# XStick__XS1-L4.net
KiCad netlist of a schematic drawn in EAGLE
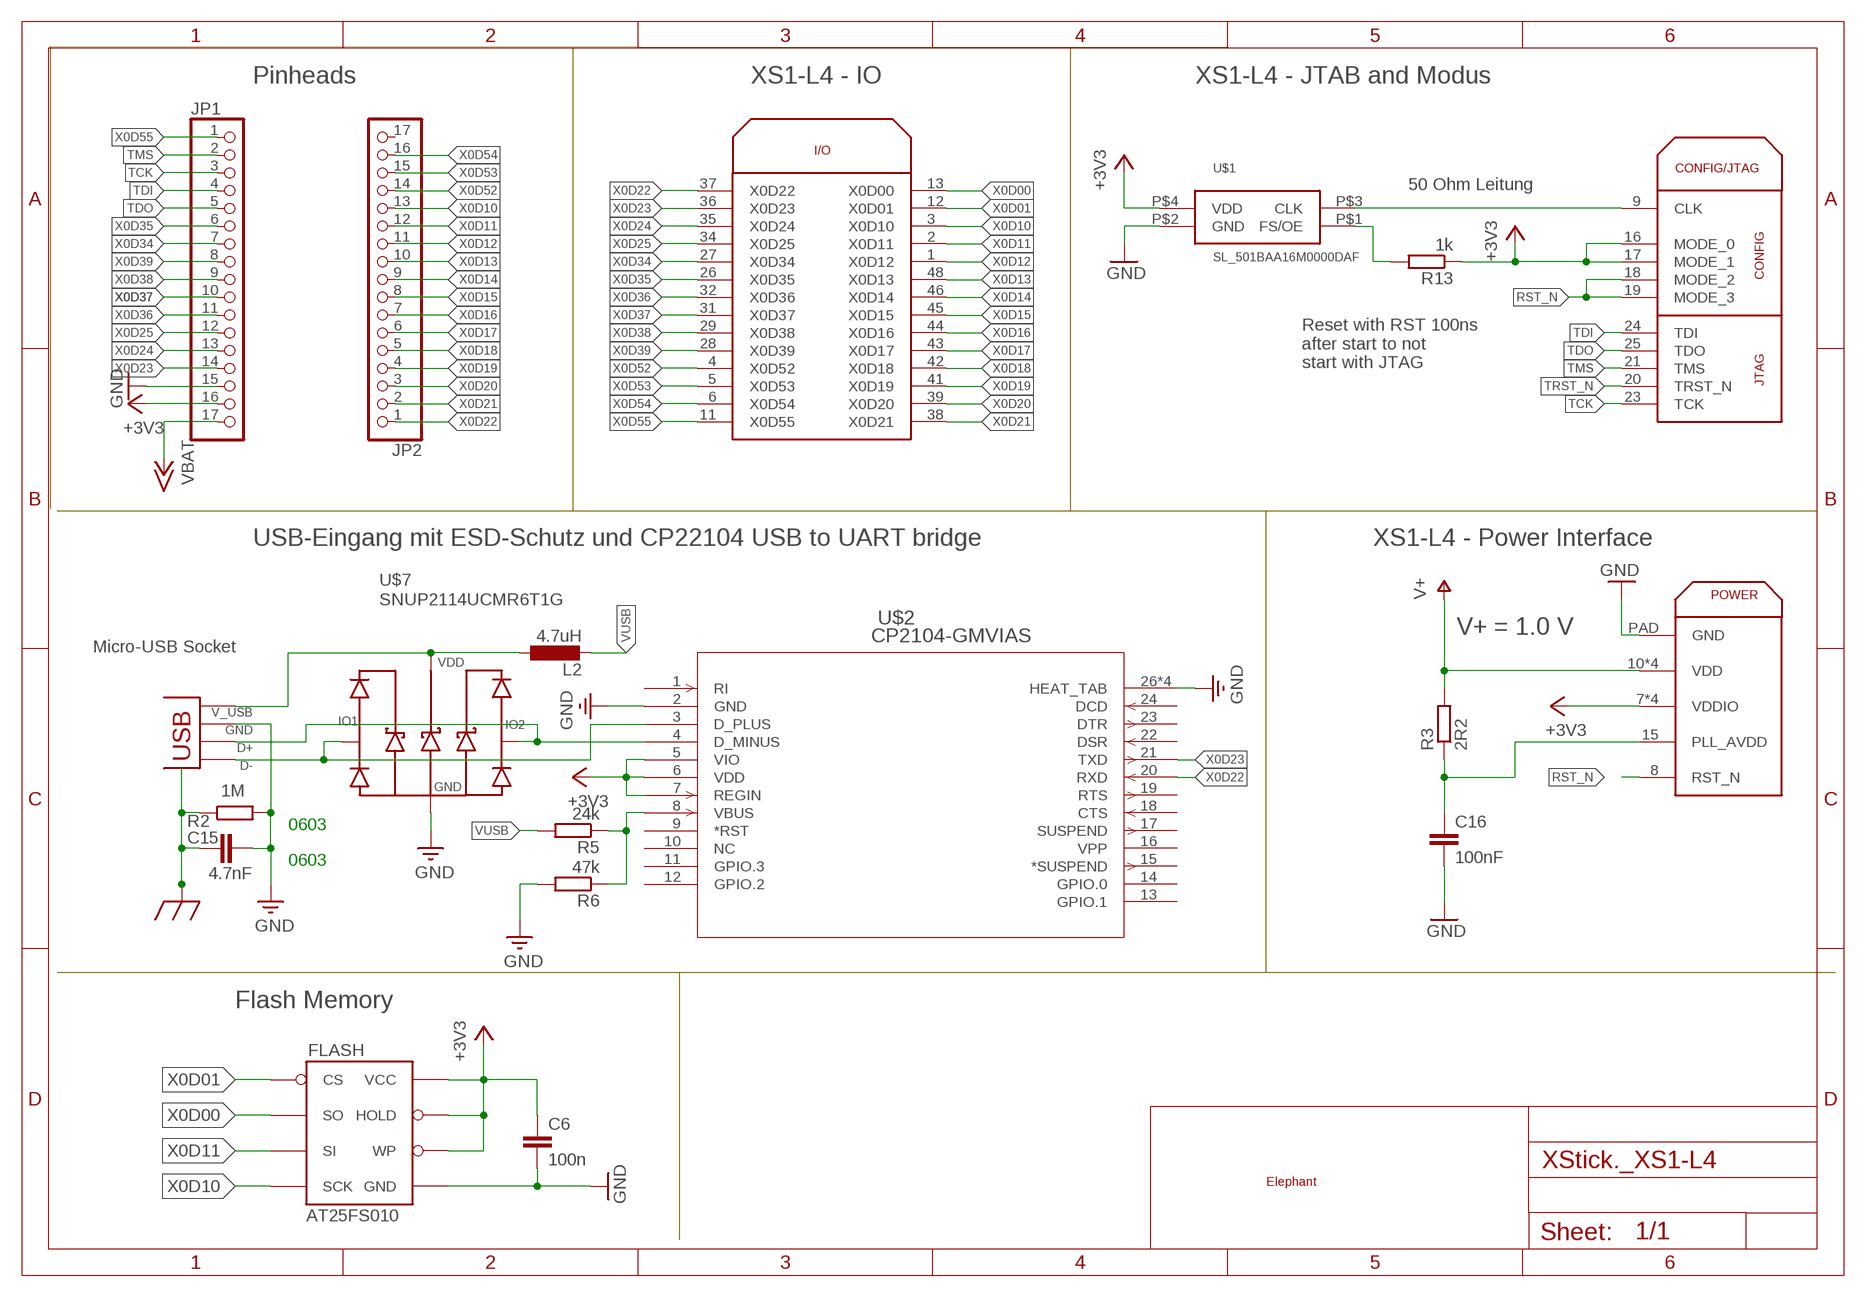
[diagram p0: schematic, sheet 1, part 1 of 2]
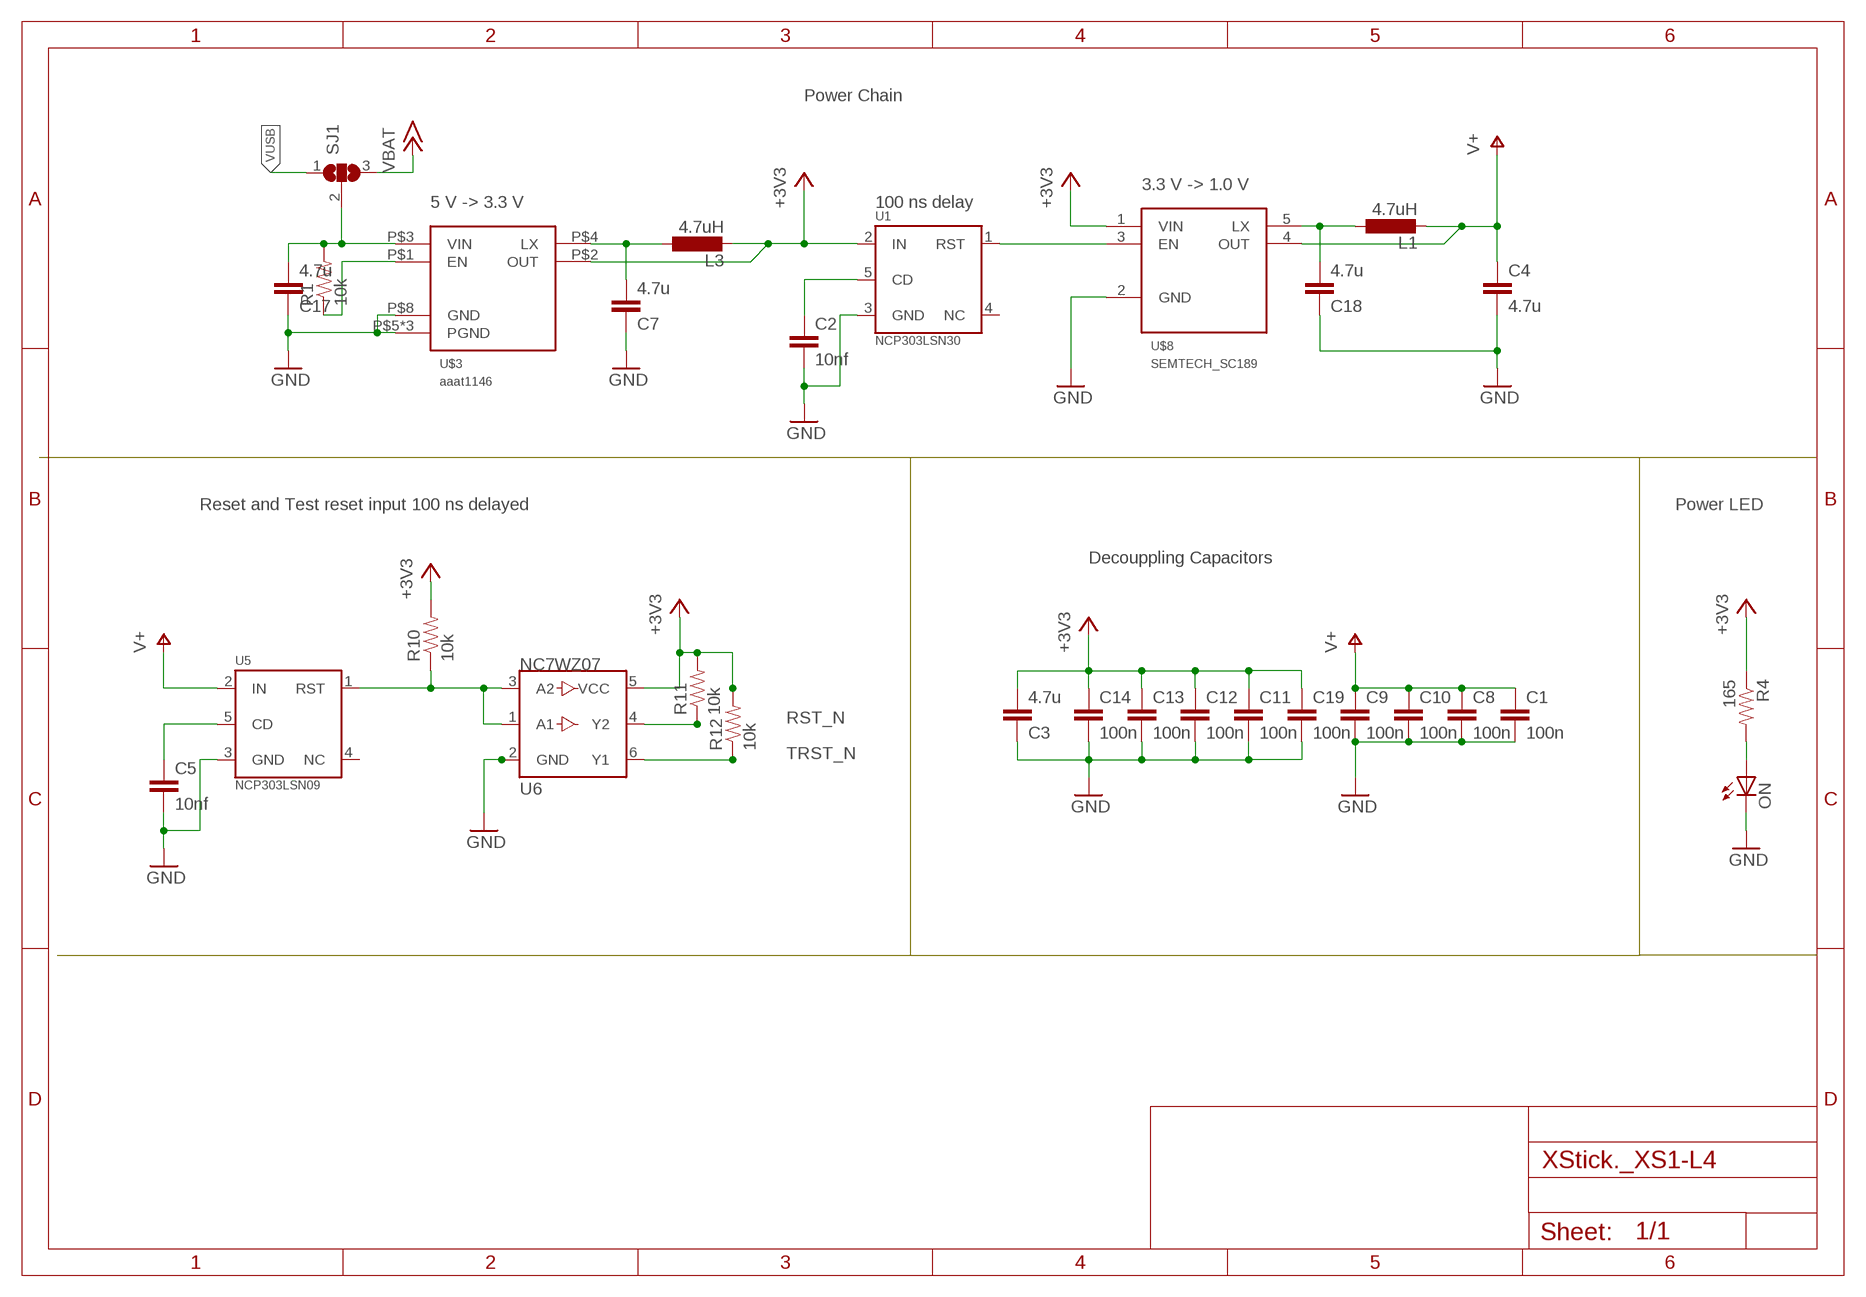
[diagram p1: schematic, sheet 1, part 2 of 2]

(export (version "E")
  (design (tool "Eeschema 10.0.6"))
  (components
    (comp (ref "C1")
      (value "100n")
      (footprint "eagle-import:C0402")
      (libsource (lib "eagle-import") (part "C-EUC0402"))
    )
    (comp (ref "C2")
      (value "10nf")
      (footprint "eagle-import:0603-CAP")
      (libsource (lib "eagle-import") (part "CAP0603-CAP"))
    )
    (comp (ref "C3")
      (value "4.7u")
      (footprint "eagle-import:0603-CAP")
      (libsource (lib "eagle-import") (part "CAP0603-CAP"))
    )
    (comp (ref "C4")
      (value "4.7u")
      (footprint "eagle-import:0603-CAP")
      (libsource (lib "eagle-import") (part "CAP0603-CAP"))
    )
    (comp (ref "C5")
      (value "10nf")
      (footprint "eagle-import:0603-CAP")
      (libsource (lib "eagle-import") (part "CAP0603-CAP"))
    )
    (comp (ref "C6")
      (value "100n")
      (footprint "eagle-import:C0402")
      (libsource (lib "eagle-import") (part "C-EUC0402"))
    )
    (comp (ref "C7")
      (value "4.7u")
      (footprint "eagle-import:0603-CAP")
      (libsource (lib "eagle-import") (part "CAP0603-CAP"))
    )
    (comp (ref "C8")
      (value "100n")
      (footprint "eagle-import:C0402")
      (libsource (lib "eagle-import") (part "C-EUC0402"))
    )
    (comp (ref "C9")
      (value "100n")
      (footprint "eagle-import:C0402")
      (libsource (lib "eagle-import") (part "C-EUC0402"))
    )
    (comp (ref "C10")
      (value "100n")
      (footprint "eagle-import:C0402")
      (libsource (lib "eagle-import") (part "C-EUC0402"))
    )
    (comp (ref "C11")
      (value "100n")
      (footprint "eagle-import:C0402")
      (libsource (lib "eagle-import") (part "C-EUC0402"))
    )
    (comp (ref "C12")
      (value "100n")
      (footprint "eagle-import:C0402")
      (libsource (lib "eagle-import") (part "C-EUC0402"))
    )
    (comp (ref "C13")
      (value "100n")
      (footprint "eagle-import:C0402")
      (libsource (lib "eagle-import") (part "C-EUC0402"))
    )
    (comp (ref "C14")
      (value "100n")
      (footprint "eagle-import:C0402")
      (libsource (lib "eagle-import") (part "C-EUC0402"))
    )
    (comp (ref "C15")
      (value "4.7nF")
      (footprint "eagle-import:C0603M")
      (libsource (lib "eagle-import") (part "C_EU0603MARK"))
    )
    (comp (ref "C16")
      (value "100nF")
      (footprint "eagle-import:C0402")
      (libsource (lib "eagle-import") (part "C-EUC0402"))
    )
    (comp (ref "C17")
      (value "4.7u")
      (footprint "eagle-import:0603-CAP")
      (libsource (lib "eagle-import") (part "CAP0603-CAP"))
    )
    (comp (ref "C18")
      (value "4.7u")
      (footprint "eagle-import:0603-CAP")
      (libsource (lib "eagle-import") (part "CAP0603-CAP"))
    )
    (comp (ref "C19")
      (value "100n")
      (footprint "eagle-import:C0402")
      (libsource (lib "eagle-import") (part "C-EUC0402"))
    )
    (comp (ref "FLASH")
      (value "AT25FS010")
      (footprint "eagle-import:SO08WIDE")
      (libsource (lib "eagle-import") (part "AT25FS010"))
    )
    (comp (ref "JP1")
      (value "PINHD-1X17")
      (footprint "eagle-import:1X17")
      (libsource (lib "eagle-import") (part "PINHD-1X17"))
    )
    (comp (ref "JP2")
      (value "PINHD-1X17")
      (footprint "eagle-import:1X17")
      (libsource (lib "eagle-import") (part "PINHD-1X17"))
    )
    (comp (ref "L1")
      (value "4.7uH")
      (footprint "eagle-import:C0603")
      (libsource (lib "eagle-import") (part "L-EUL0603"))
    )
    (comp (ref "L2")
      (value "4.7uH")
      (footprint "eagle-import:C0603")
      (libsource (lib "eagle-import") (part "L-EUL0603"))
    )
    (comp (ref "L3")
      (value "4.7uH")
      (footprint "eagle-import:C0603")
      (libsource (lib "eagle-import") (part "L-EUL0603"))
    )
    (comp (ref "ON")
      (value "LED0603")
      (footprint "eagle-import:LED-0603")
      (libsource (lib "eagle-import") (part "LED0603"))
    )
    (comp (ref "R1")
      (value "10k")
      (footprint "eagle-import:0603-RES")
      (libsource (lib "eagle-import") (part "RESISTOR0603-RES"))
    )
    (comp (ref "R2")
      (value "1M")
      (footprint "eagle-import:R0603M")
      (libsource (lib "eagle-import") (part "RESISTOR0603MARK"))
    )
    (comp (ref "R3")
      (value "2R2")
      (footprint "eagle-import:R0603")
      (libsource (lib "eagle-import") (part "R-EU_R0603"))
    )
    (comp (ref "R4")
      (value "165")
      (footprint "eagle-import:0603-RES")
      (libsource (lib "eagle-import") (part "RESISTOR0603-RES"))
    )
    (comp (ref "R5")
      (value "24k")
      (footprint "eagle-import:R0603")
      (libsource (lib "eagle-import") (part "R-EU_R0603"))
    )
    (comp (ref "R6")
      (value "47k")
      (footprint "eagle-import:R0603")
      (libsource (lib "eagle-import") (part "R-EU_R0603"))
    )
    (comp (ref "R10")
      (value "10k")
      (footprint "eagle-import:0603-RES")
      (libsource (lib "eagle-import") (part "RESISTOR0603-RES"))
    )
    (comp (ref "R11")
      (value "10k")
      (footprint "eagle-import:0603-RES")
      (libsource (lib "eagle-import") (part "RESISTOR0603-RES"))
    )
    (comp (ref "R12")
      (value "10k")
      (footprint "eagle-import:0603-RES")
      (libsource (lib "eagle-import") (part "RESISTOR0603-RES"))
    )
    (comp (ref "R13")
      (value "1k")
      (footprint "eagle-import:R0603")
      (libsource (lib "eagle-import") (part "R-EU_R0603"))
    )
    (comp (ref "SJ1")
      (value "SJ2W")
      (footprint "eagle-import:SJ_2")
      (libsource (lib "eagle-import") (part "SJ2W"))
    )
    (comp (ref "U$1")
      (value "SL_501BAA16M0000DAF")
      (footprint "eagle-import:SL_OSZ")
      (libsource (lib "eagle-import") (part "SL_501BAA16M0000DAF"))
    )
    (comp (ref "U$2")
      (value "CP2104-GMVIAS")
      (footprint "eagle-import:QFN24_4X4_VIAS")
      (libsource (lib "eagle-import") (part "CP2104-GMVIAS"))
    )
    (comp (ref "U$3")
      (value "aaat1146")
      (footprint "eagle-import:SC70JW-8")
      (libsource (lib "eagle-import") (part "SKYWORKS_AAT1146_SC70JW-8"))
    )
    (comp (ref "U$4")
      (value "ELEPHANT")
      (footprint "eagle-import:ELEPHANT")
      (libsource (lib "eagle-import") (part "ELEPHANT"))
    )
    (comp (ref "U$5")
      (value "XS1-L01A-TQ48")
      (footprint "eagle-import:TQFP48")
      (libsource (lib "eagle-import") (part "XS1-L01A-TQ48"))
    )
    (comp (ref "U$7")
      (value "SNUP2114UCMR6T1G")
      (footprint "eagle-import:TSOP-6")
      (libsource (lib "eagle-import") (part "SNUP2114UCMR6T1G"))
    )
    (comp (ref "U$8")
      (value "SEMTECH_SC189")
      (footprint "eagle-import:SOT23-5")
      (libsource (lib "eagle-import") (part "SEMTECH_SC189"))
    )
    (comp (ref "U1")
      (value "NCP303LSN30")
      (footprint "eagle-import:SOT23-5")
      (libsource (lib "eagle-import") (part "NCP303LSN09"))
    )
    (comp (ref "U5")
      (value "NCP303LSN09")
      (footprint "eagle-import:SOT23-5")
      (libsource (lib "eagle-import") (part "NCP303LSN09"))
    )
    (comp (ref "U6")
      (value "NC7WZ07")
      (footprint "eagle-import:SC70-6")
      (libsource (lib "eagle-import") (part "NC7WZ07"))
    )
    (comp (ref "USB_SKT")
      (value "USB_SHIELD_8")
      (footprint "eagle-import:USB_MICRO_B")
      (libsource (lib "eagle-import") (part "USB_SHIELD_8"))
    )
  )
  (nets
    (net (code "1") (name "+3V3") (class "Default")
      (node (ref "C11") (pin "1") (pinfunction "1_1") (pintype "passive"))
      (node (ref "C12") (pin "1") (pinfunction "1_1") (pintype "passive"))
      (node (ref "C13") (pin "1") (pinfunction "1_1") (pintype "passive"))
      (node (ref "C14") (pin "1") (pinfunction "1_1") (pintype "passive"))
      (node (ref "C19") (pin "1") (pinfunction "1_1") (pintype "passive"))
      (node (ref "C3") (pin "2") (pinfunction "2_2") (pintype "passive"))
      (node (ref "C6") (pin "1") (pinfunction "1_1") (pintype "passive"))
      (node (ref "FLASH") (pin "3") (pinfunction "WP_3") (pintype "bidirectional"))
      (node (ref "FLASH") (pin "7") (pinfunction "HOLD_7") (pintype "bidirectional"))
      (node (ref "FLASH") (pin "8") (pinfunction "VCC_8") (pintype "bidirectional"))
      (node (ref "JP1") (pin "16") (pinfunction "16_16") (pintype "passive"))
      (node (ref "L3") (pin "2") (pinfunction "2_2") (pintype "passive"))
      (node (ref "R10") (pin "2") (pinfunction "2_2") (pintype "passive"))
      (node (ref "R11") (pin "2") (pinfunction "2_2") (pintype "passive"))
      (node (ref "R12") (pin "2") (pinfunction "2_2") (pintype "passive"))
      (node (ref "R13") (pin "1") (pinfunction "1_1") (pintype "passive"))
      (node (ref "R4") (pin "1") (pinfunction "1_1") (pintype "passive"))
      (node (ref "U$1") (pin "P$4") (pinfunction "VDD_P$4") (pintype "bidirectional"))
      (node (ref "U$2") (pin "5") (pinfunction "VIO_5") (pintype "power_in"))
      (node (ref "U$2") (pin "6") (pinfunction "VDD_6") (pintype "power_in"))
      (node (ref "U$2") (pin "7") (pinfunction "REGIN_7") (pintype "input"))
      (node (ref "U$3") (pin "P$2") (pinfunction "OUT_P$2") (pintype "bidirectional"))
      (node (ref "U$5") (pin "14") (pinfunction "VDDIO_14") (pintype "bidirectional"))
      (node (ref "U$5") (pin "16") (pinfunction "MODE_0_16") (pintype "bidirectional"))
      (node (ref "U$5") (pin "17") (pinfunction "MODE_1_17") (pintype "bidirectional"))
      (node (ref "U$5") (pin "30") (pinfunction "VDDIO_30") (pintype "bidirectional"))
      (node (ref "U$5") (pin "40") (pinfunction "VDDIO_40") (pintype "bidirectional"))
      (node (ref "U$5") (pin "7") (pinfunction "VDDIO_7") (pintype "bidirectional"))
      (node (ref "U$8") (pin "1") (pinfunction "VIN_1") (pintype "bidirectional"))
      (node (ref "U1") (pin "2") (pinfunction "IN_2") (pintype "bidirectional"))
      (node (ref "U6") (pin "5") (pinfunction "VCC_5") (pintype "bidirectional"))
    )
    (net (code "2") (name "GND") (class "Default")
      (node (ref "C1") (pin "2") (pinfunction "2_2") (pintype "passive"))
      (node (ref "C10") (pin "2") (pinfunction "2_2") (pintype "passive"))
      (node (ref "C11") (pin "2") (pinfunction "2_2") (pintype "passive"))
      (node (ref "C12") (pin "2") (pinfunction "2_2") (pintype "passive"))
      (node (ref "C13") (pin "2") (pinfunction "2_2") (pintype "passive"))
      (node (ref "C14") (pin "2") (pinfunction "2_2") (pintype "passive"))
      (node (ref "C15") (pin "1") (pinfunction "1_1") (pintype "passive"))
      (node (ref "C16") (pin "2") (pinfunction "2_2") (pintype "passive"))
      (node (ref "C17") (pin "1") (pinfunction "1_1") (pintype "passive"))
      (node (ref "C18") (pin "1") (pinfunction "1_1") (pintype "passive"))
      (node (ref "C19") (pin "2") (pinfunction "2_2") (pintype "passive"))
      (node (ref "C2") (pin "2") (pinfunction "2_2") (pintype "passive"))
      (node (ref "C3") (pin "1") (pinfunction "1_1") (pintype "passive"))
      (node (ref "C4") (pin "2") (pinfunction "2_2") (pintype "passive"))
      (node (ref "C5") (pin "2") (pinfunction "2_2") (pintype "passive"))
      (node (ref "C6") (pin "2") (pinfunction "2_2") (pintype "passive"))
      (node (ref "C7") (pin "1") (pinfunction "1_1") (pintype "passive"))
      (node (ref "C8") (pin "2") (pinfunction "2_2") (pintype "passive"))
      (node (ref "C9") (pin "2") (pinfunction "2_2") (pintype "passive"))
      (node (ref "FLASH") (pin "4") (pinfunction "GND_4") (pintype "bidirectional"))
      (node (ref "JP1") (pin "15") (pinfunction "15_15") (pintype "passive"))
      (node (ref "ON") (pin "C") (pinfunction "C_C") (pintype "passive"))
      (node (ref "R2") (pin "2") (pinfunction "2_2") (pintype "passive"))
      (node (ref "R6") (pin "2") (pinfunction "2_2") (pintype "passive"))
      (node (ref "U$1") (pin "P$2") (pinfunction "GND_P$2") (pintype "bidirectional"))
      (node (ref "U$2") (pin "2") (pinfunction "GND_2") (pintype "power_in"))
      (node (ref "U$2") (pin "26") (pinfunction "HEAT_TAB_26") (pintype "passive"))
      (node (ref "U$2") (pin "27") (pinfunction "HEAT_TAB_27") (pintype "passive"))
      (node (ref "U$2") (pin "28") (pinfunction "HEAT_TAB_28") (pintype "passive"))
      (node (ref "U$2") (pin "29") (pinfunction "HEAT_TAB_29") (pintype "passive"))
      (node (ref "U$3") (pin "P$5") (pinfunction "PGND_P$5") (pintype "bidirectional"))
      (node (ref "U$3") (pin "P$6") (pinfunction "PGND_P$6") (pintype "bidirectional"))
      (node (ref "U$3") (pin "P$7") (pinfunction "PGND_P$7") (pintype "bidirectional"))
      (node (ref "U$3") (pin "P$8") (pinfunction "GND_P$8") (pintype "bidirectional"))
      (node (ref "U$5") (pin "PAD") (pinfunction "GND_PAD") (pintype "bidirectional"))
      (node (ref "U$7") (pin "2") (pinfunction "VN_2") (pintype "passive"))
      (node (ref "U$8") (pin "2") (pinfunction "GND_2") (pintype "bidirectional"))
      (node (ref "U1") (pin "3") (pinfunction "GND_3") (pintype "bidirectional"))
      (node (ref "U5") (pin "3") (pinfunction "GND_3") (pintype "bidirectional"))
      (node (ref "U6") (pin "2") (pinfunction "GND_2") (pintype "bidirectional"))
      (node (ref "USB_SKT") (pin "GND") (pinfunction "GND_GND") (pintype "power_in"))
    )
    (net (code "3") (name "Net-(ON-PadA)") (class "Default")
      (node (ref "ON") (pin "A") (pinfunction "A_A") (pintype "passive"))
      (node (ref "R4") (pin "2") (pinfunction "2_2") (pintype "passive"))
    )
    (net (code "4") (name "Net-(U$1-CLK)") (class "Default")
      (node (ref "U$1") (pin "P$3") (pinfunction "CLK_P$3") (pintype "bidirectional"))
      (node (ref "U$5") (pin "9") (pinfunction "CLK_9") (pintype "bidirectional"))
    )
    (net (code "5") (name "Net-(U$1-FS{slash}OE)") (class "Default")
      (node (ref "R13") (pin "2") (pinfunction "2_2") (pintype "passive"))
      (node (ref "U$1") (pin "P$1") (pinfunction "FS/OE_P$1") (pintype "bidirectional"))
    )
    (net (code "6") (name "Net-(U$2-D_MINUS)") (class "Default")
      (node (ref "U$2") (pin "4") (pinfunction "D_MINUS_4") (pintype "passive"))
      (node (ref "U$7") (pin "1") (pinfunction "I/O1_1") (pintype "passive"))
      (node (ref "USB_SKT") (pin "D+") (pinfunction "D+_D+") (pintype "bidirectional"))
    )
    (net (code "7") (name "Net-(U$2-D_PLUS)") (class "Default")
      (node (ref "U$2") (pin "3") (pinfunction "D_PLUS_3") (pintype "passive"))
      (node (ref "U$7") (pin "6") (pinfunction "I/O2_6") (pintype "passive"))
      (node (ref "USB_SKT") (pin "D-") (pinfunction "D-_D-") (pintype "bidirectional"))
    )
    (net (code "8") (name "Net-(U$2-VBUS)") (class "Default")
      (node (ref "R5") (pin "1") (pinfunction "1_1") (pintype "passive"))
      (node (ref "R6") (pin "1") (pinfunction "1_1") (pintype "passive"))
      (node (ref "U$2") (pin "8") (pinfunction "VBUS_8") (pintype "input"))
    )
    (net (code "9") (name "Net-(U$3-EN)") (class "Default")
      (node (ref "R1") (pin "1") (pinfunction "1_1") (pintype "passive"))
      (node (ref "U$3") (pin "P$1") (pinfunction "EN_P$1") (pintype "bidirectional"))
    )
    (net (code "10") (name "Net-(U$3-LX)") (class "Default")
      (node (ref "C7") (pin "2") (pinfunction "2_2") (pintype "passive"))
      (node (ref "L3") (pin "1") (pinfunction "1_1") (pintype "passive"))
      (node (ref "U$3") (pin "P$4") (pinfunction "LX_P$4") (pintype "bidirectional"))
    )
    (net (code "11") (name "Net-(U$3-VIN)") (class "Default")
      (node (ref "C17") (pin "2") (pinfunction "2_2") (pintype "passive"))
      (node (ref "R1") (pin "2") (pinfunction "2_2") (pintype "passive"))
      (node (ref "SJ1") (pin "2") (pinfunction "2_2") (pintype "passive"))
      (node (ref "U$3") (pin "P$3") (pinfunction "VIN_P$3") (pintype "bidirectional"))
    )
    (net (code "12") (name "Net-(U$5C-PLL_AVDD)") (class "Default")
      (node (ref "C16") (pin "1") (pinfunction "1_1") (pintype "passive"))
      (node (ref "R3") (pin "1") (pinfunction "1_1") (pintype "passive"))
      (node (ref "U$5") (pin "15") (pinfunction "PLL_AVDD_15") (pintype "bidirectional"))
    )
    (net (code "13") (name "Net-(U$7-VP)") (class "Default")
      (node (ref "L2") (pin "1") (pinfunction "1_1") (pintype "passive"))
      (node (ref "U$7") (pin "5") (pinfunction "VP_5") (pintype "passive"))
      (node (ref "USB_SKT") (pin "VBUS") (pinfunction "V_USB_VBUS") (pintype "power_in"))
    )
    (net (code "14") (name "Net-(U$8-EN)") (class "Default")
      (node (ref "U$8") (pin "3") (pinfunction "EN_3") (pintype "bidirectional"))
      (node (ref "U1") (pin "1") (pinfunction "RST_1") (pintype "bidirectional"))
    )
    (net (code "15") (name "Net-(U$8-LX)") (class "Default")
      (node (ref "C18") (pin "2") (pinfunction "2_2") (pintype "passive"))
      (node (ref "L1") (pin "1") (pinfunction "1_1") (pintype "passive"))
      (node (ref "U$8") (pin "5") (pinfunction "LX_5") (pintype "bidirectional"))
    )
    (net (code "16") (name "Net-(U1-CD)") (class "Default")
      (node (ref "C2") (pin "1") (pinfunction "1_1") (pintype "passive"))
      (node (ref "U1") (pin "5") (pinfunction "CD_5") (pintype "bidirectional"))
    )
    (net (code "17") (name "Net-(U5-CD)") (class "Default")
      (node (ref "C5") (pin "1") (pinfunction "1_1") (pintype "passive"))
      (node (ref "U5") (pin "5") (pinfunction "CD_5") (pintype "bidirectional"))
    )
    (net (code "18") (name "Net-(U5-RST)") (class "Default")
      (node (ref "R10") (pin "1") (pinfunction "1_1") (pintype "passive"))
      (node (ref "U5") (pin "1") (pinfunction "RST_1") (pintype "bidirectional"))
      (node (ref "U6") (pin "1") (pinfunction "A1_1") (pintype "bidirectional"))
      (node (ref "U6") (pin "3") (pinfunction "A2_3") (pintype "bidirectional"))
    )
    (net (code "19") (name "Net-(USB_SKTB-SHIELD$1)") (class "Default")
      (node (ref "C15") (pin "2") (pinfunction "2_2") (pintype "passive"))
      (node (ref "R2") (pin "1") (pinfunction "1_1") (pintype "passive"))
      (node (ref "USB_SKT") (pin "SHIELD$1") (pinfunction "SHIELD$1_SHIELD$1") (pintype "power_in"))
      (node (ref "USB_SKT") (pin "SHIELD$2") (pinfunction "SHIELD$1_SHIELD$2") (pintype "power_in"))
      (node (ref "USB_SKT") (pin "SHIELD$3") (pinfunction "SHIELD$1_SHIELD$3") (pintype "power_in"))
      (node (ref "USB_SKT") (pin "SHIELD$4") (pinfunction "SHIELD$1_SHIELD$4") (pintype "power_in"))
      (node (ref "USB_SKT") (pin "SHIELD$5") (pinfunction "SHIELD$1_SHIELD$5") (pintype "power_in"))
      (node (ref "USB_SKT") (pin "SHIELD$6") (pinfunction "SHIELD$1_SHIELD$6") (pintype "power_in"))
      (node (ref "USB_SKT") (pin "SHIELD$7") (pinfunction "SHIELD$1_SHIELD$7") (pintype "power_in"))
      (node (ref "USB_SKT") (pin "SHIELD$8") (pinfunction "SHIELD$1_SHIELD$8") (pintype "power_in"))
    )
    (net (code "20") (name "RST_N") (class "Default")
      (node (ref "R11") (pin "1") (pinfunction "1_1") (pintype "passive"))
      (node (ref "U$5") (pin "18") (pinfunction "MODE_2_18") (pintype "bidirectional"))
      (node (ref "U$5") (pin "19") (pinfunction "MODE_3_19") (pintype "bidirectional"))
      (node (ref "U$5") (pin "8") (pinfunction "RST_N_8") (pintype "bidirectional"))
      (node (ref "U6") (pin "4") (pinfunction "Y2_4") (pintype "bidirectional"))
    )
    (net (code "21") (name "TCK") (class "Default")
      (node (ref "JP1") (pin "3") (pinfunction "3_3") (pintype "passive"))
      (node (ref "U$5") (pin "23") (pinfunction "TCK_23") (pintype "bidirectional"))
    )
    (net (code "22") (name "TDI") (class "Default")
      (node (ref "JP1") (pin "4") (pinfunction "4_4") (pintype "passive"))
      (node (ref "U$5") (pin "24") (pinfunction "TDI_24") (pintype "bidirectional"))
    )
    (net (code "23") (name "TDO") (class "Default")
      (node (ref "JP1") (pin "5") (pinfunction "5_5") (pintype "passive"))
      (node (ref "U$5") (pin "25") (pinfunction "TDO_25") (pintype "bidirectional"))
    )
    (net (code "24") (name "TMS") (class "Default")
      (node (ref "JP1") (pin "2") (pinfunction "2_2") (pintype "passive"))
      (node (ref "U$5") (pin "21") (pinfunction "TMS_21") (pintype "bidirectional"))
    )
    (net (code "25") (name "TRST_N") (class "Default")
      (node (ref "R12") (pin "1") (pinfunction "1_1") (pintype "passive"))
      (node (ref "U$5") (pin "20") (pinfunction "TRST_N_20") (pintype "bidirectional"))
      (node (ref "U6") (pin "6") (pinfunction "Y1_6") (pintype "bidirectional"))
    )
    (net (code "26") (name "V+") (class "Default")
      (node (ref "C1") (pin "1") (pinfunction "1_1") (pintype "passive"))
      (node (ref "C10") (pin "1") (pinfunction "1_1") (pintype "passive"))
      (node (ref "C4") (pin "1") (pinfunction "1_1") (pintype "passive"))
      (node (ref "C8") (pin "1") (pinfunction "1_1") (pintype "passive"))
      (node (ref "C9") (pin "1") (pinfunction "1_1") (pintype "passive"))
      (node (ref "L1") (pin "2") (pinfunction "2_2") (pintype "passive"))
      (node (ref "R3") (pin "2") (pinfunction "2_2") (pintype "passive"))
      (node (ref "U$5") (pin "10") (pinfunction "VDD_10") (pintype "bidirectional"))
      (node (ref "U$5") (pin "22") (pinfunction "VDD_22") (pintype "bidirectional"))
      (node (ref "U$5") (pin "33") (pinfunction "VDD_33") (pintype "bidirectional"))
      (node (ref "U$5") (pin "47") (pinfunction "VDD_47") (pintype "bidirectional"))
      (node (ref "U$8") (pin "4") (pinfunction "OUT_4") (pintype "bidirectional"))
      (node (ref "U5") (pin "2") (pinfunction "IN_2") (pintype "bidirectional"))
    )
    (net (code "27") (name "VBAT") (class "Default")
      (node (ref "JP1") (pin "17") (pinfunction "17_17") (pintype "passive"))
      (node (ref "SJ1") (pin "3") (pinfunction "3_3") (pintype "passive"))
    )
    (net (code "28") (name "VUSB") (class "Default")
      (node (ref "L2") (pin "2") (pinfunction "2_2") (pintype "passive"))
      (node (ref "R5") (pin "2") (pinfunction "2_2") (pintype "passive"))
      (node (ref "SJ1") (pin "1") (pinfunction "1_1") (pintype "passive"))
    )
    (net (code "29") (name "X0D00") (class "Default")
      (node (ref "FLASH") (pin "2") (pinfunction "SO_2") (pintype "bidirectional"))
      (node (ref "U$5") (pin "13") (pinfunction "X0D00_13") (pintype "bidirectional"))
    )
    (net (code "30") (name "X0D01") (class "Default")
      (node (ref "FLASH") (pin "1") (pinfunction "CS_1") (pintype "bidirectional"))
      (node (ref "U$5") (pin "12") (pinfunction "X0D01_12") (pintype "bidirectional"))
    )
    (net (code "31") (name "X0D10") (class "Default")
      (node (ref "FLASH") (pin "6") (pinfunction "SCK_6") (pintype "bidirectional"))
      (node (ref "JP2") (pin "13") (pinfunction "13_13") (pintype "passive"))
      (node (ref "U$5") (pin "3") (pinfunction "X0D10_3") (pintype "bidirectional"))
    )
    (net (code "32") (name "X0D11") (class "Default")
      (node (ref "FLASH") (pin "5") (pinfunction "SI_5") (pintype "bidirectional"))
      (node (ref "JP2") (pin "12") (pinfunction "12_12") (pintype "passive"))
      (node (ref "U$5") (pin "2") (pinfunction "X0D11_2") (pintype "bidirectional"))
    )
    (net (code "33") (name "X0D12") (class "Default")
      (node (ref "JP2") (pin "11") (pinfunction "11_11") (pintype "passive"))
      (node (ref "U$5") (pin "1") (pinfunction "X0D12_1") (pintype "bidirectional"))
    )
    (net (code "34") (name "X0D13") (class "Default")
      (node (ref "JP2") (pin "10") (pinfunction "10_10") (pintype "passive"))
      (node (ref "U$5") (pin "48") (pinfunction "X0D13_48") (pintype "bidirectional"))
    )
    (net (code "35") (name "X0D14") (class "Default")
      (node (ref "JP2") (pin "9") (pinfunction "9_9") (pintype "passive"))
      (node (ref "U$5") (pin "46") (pinfunction "X0D14_46") (pintype "bidirectional"))
    )
    (net (code "36") (name "X0D15") (class "Default")
      (node (ref "JP2") (pin "8") (pinfunction "8_8") (pintype "passive"))
      (node (ref "U$5") (pin "45") (pinfunction "X0D15_45") (pintype "bidirectional"))
    )
    (net (code "37") (name "X0D16") (class "Default")
      (node (ref "JP2") (pin "7") (pinfunction "7_7") (pintype "passive"))
      (node (ref "U$5") (pin "44") (pinfunction "X0D16_44") (pintype "bidirectional"))
    )
    (net (code "38") (name "X0D17") (class "Default")
      (node (ref "JP2") (pin "6") (pinfunction "6_6") (pintype "passive"))
      (node (ref "U$5") (pin "43") (pinfunction "X0D17_43") (pintype "bidirectional"))
    )
    (net (code "39") (name "X0D18") (class "Default")
      (node (ref "JP2") (pin "5") (pinfunction "5_5") (pintype "passive"))
      (node (ref "U$5") (pin "42") (pinfunction "X0D18_42") (pintype "bidirectional"))
    )
    (net (code "40") (name "X0D19") (class "Default")
      (node (ref "JP2") (pin "4") (pinfunction "4_4") (pintype "passive"))
      (node (ref "U$5") (pin "41") (pinfunction "X0D19_41") (pintype "bidirectional"))
    )
    (net (code "41") (name "X0D20") (class "Default")
      (node (ref "JP2") (pin "3") (pinfunction "3_3") (pintype "passive"))
      (node (ref "U$5") (pin "39") (pinfunction "X0D20_39") (pintype "bidirectional"))
    )
    (net (code "42") (name "X0D21") (class "Default")
      (node (ref "JP2") (pin "2") (pinfunction "2_2") (pintype "passive"))
      (node (ref "U$5") (pin "38") (pinfunction "X0D21_38") (pintype "bidirectional"))
    )
    (net (code "43") (name "X0D22") (class "Default")
      (node (ref "JP2") (pin "1") (pinfunction "1_1") (pintype "passive"))
      (node (ref "U$2") (pin "20") (pinfunction "RXD_20") (pintype "input"))
      (node (ref "U$5") (pin "37") (pinfunction "X0D22_37") (pintype "bidirectional"))
    )
    (net (code "44") (name "X0D23") (class "Default")
      (node (ref "JP1") (pin "14") (pinfunction "14_14") (pintype "passive"))
      (node (ref "U$2") (pin "21") (pinfunction "TXD_21") (pintype "output"))
      (node (ref "U$5") (pin "36") (pinfunction "X0D23_36") (pintype "bidirectional"))
    )
    (net (code "45") (name "X0D24") (class "Default")
      (node (ref "JP1") (pin "13") (pinfunction "13_13") (pintype "passive"))
      (node (ref "U$5") (pin "35") (pinfunction "X0D24_35") (pintype "bidirectional"))
    )
    (net (code "46") (name "X0D25") (class "Default")
      (node (ref "JP1") (pin "12") (pinfunction "12_12") (pintype "passive"))
      (node (ref "U$5") (pin "34") (pinfunction "X0D25_34") (pintype "bidirectional"))
    )
    (net (code "47") (name "X0D34") (class "Default")
      (node (ref "JP1") (pin "7") (pinfunction "7_7") (pintype "passive"))
      (node (ref "U$5") (pin "27") (pinfunction "X0D34_27") (pintype "bidirectional"))
    )
    (net (code "48") (name "X0D35") (class "Default")
      (node (ref "JP1") (pin "6") (pinfunction "6_6") (pintype "passive"))
      (node (ref "U$5") (pin "26") (pinfunction "X0D35_26") (pintype "bidirectional"))
    )
    (net (code "49") (name "X0D36") (class "Default")
      (node (ref "JP1") (pin "11") (pinfunction "11_11") (pintype "passive"))
      (node (ref "U$5") (pin "32") (pinfunction "X0D36_32") (pintype "bidirectional"))
    )
    (net (code "50") (name "X0D37") (class "Default")
      (node (ref "JP1") (pin "10") (pinfunction "10_10") (pintype "passive"))
      (node (ref "U$5") (pin "31") (pinfunction "X0D37_31") (pintype "bidirectional"))
    )
    (net (code "51") (name "X0D38") (class "Default")
      (node (ref "JP1") (pin "9") (pinfunction "9_9") (pintype "passive"))
      (node (ref "U$5") (pin "29") (pinfunction "X0D38_29") (pintype "bidirectional"))
    )
    (net (code "52") (name "X0D39") (class "Default")
      (node (ref "JP1") (pin "8") (pinfunction "8_8") (pintype "passive"))
      (node (ref "U$5") (pin "28") (pinfunction "X0D39_28") (pintype "bidirectional"))
    )
    (net (code "53") (name "X0D52") (class "Default")
      (node (ref "JP2") (pin "14") (pinfunction "14_14") (pintype "passive"))
      (node (ref "U$5") (pin "4") (pinfunction "X0D52_4") (pintype "bidirectional"))
    )
    (net (code "54") (name "X0D53") (class "Default")
      (node (ref "JP2") (pin "15") (pinfunction "15_15") (pintype "passive"))
      (node (ref "U$5") (pin "5") (pinfunction "X0D53_5") (pintype "bidirectional"))
    )
    (net (code "55") (name "X0D54") (class "Default")
      (node (ref "JP2") (pin "16") (pinfunction "16_16") (pintype "passive"))
      (node (ref "U$5") (pin "6") (pinfunction "X0D54_6") (pintype "bidirectional"))
    )
    (net (code "56") (name "X0D55") (class "Default")
      (node (ref "JP1") (pin "1") (pinfunction "1_1") (pintype "passive"))
      (node (ref "U$5") (pin "11") (pinfunction "X0D55_11") (pintype "bidirectional"))
    )
    (net (code "57") (name "unconnected-(JP2-Pad17)") (class "Default")
      (node (ref "JP2") (pin "17") (pinfunction "17_17") (pintype "passive"))
    )
    (net (code "58") (name "unconnected-(U$2-*RST-Pad9)") (class "Default")
      (node (ref "U$2") (pin "9") (pinfunction "*RST_9") (pintype "passive"))
    )
    (net (code "59") (name "unconnected-(U$2-*SUSPEND-Pad15)") (class "Default")
      (node (ref "U$2") (pin "15") (pinfunction "*SUSPEND_15") (pintype "output"))
    )
    (net (code "60") (name "unconnected-(U$2-CTS-Pad18)") (class "Default")
      (node (ref "U$2") (pin "18") (pinfunction "CTS_18") (pintype "input"))
    )
    (net (code "61") (name "unconnected-(U$2-DCD-Pad24)") (class "Default")
      (node (ref "U$2") (pin "24") (pinfunction "DCD_24") (pintype "input"))
    )
    (net (code "62") (name "unconnected-(U$2-DSR-Pad22)") (class "Default")
      (node (ref "U$2") (pin "22") (pinfunction "DSR_22") (pintype "input"))
    )
    (net (code "63") (name "unconnected-(U$2-DTR-Pad23)") (class "Default")
      (node (ref "U$2") (pin "23") (pinfunction "DTR_23") (pintype "output"))
    )
    (net (code "64") (name "unconnected-(U$2-GPIO.0-Pad14)") (class "Default")
      (node (ref "U$2") (pin "14") (pinfunction "GPIO.0_14") (pintype "passive"))
    )
    (net (code "65") (name "unconnected-(U$2-GPIO.1-Pad13)") (class "Default")
      (node (ref "U$2") (pin "13") (pinfunction "GPIO.1_13") (pintype "passive"))
    )
    (net (code "66") (name "unconnected-(U$2-GPIO.2-Pad12)") (class "Default")
      (node (ref "U$2") (pin "12") (pinfunction "GPIO.2_12") (pintype "passive"))
    )
    (net (code "67") (name "unconnected-(U$2-GPIO.3-Pad11)") (class "Default")
      (node (ref "U$2") (pin "11") (pinfunction "GPIO.3_11") (pintype "passive"))
    )
    (net (code "68") (name "unconnected-(U$2-NC-Pad10)") (class "Default")
      (node (ref "U$2") (pin "10") (pinfunction "NC_10") (pintype "no_connect"))
    )
    (net (code "69") (name "unconnected-(U$2-RI-Pad1)") (class "Default")
      (node (ref "U$2") (pin "1") (pinfunction "RI_1") (pintype "input"))
    )
    (net (code "70") (name "unconnected-(U$2-RTS-Pad19)") (class "Default")
      (node (ref "U$2") (pin "19") (pinfunction "RTS_19") (pintype "output"))
    )
    (net (code "71") (name "unconnected-(U$2-SUSPEND-Pad17)") (class "Default")
      (node (ref "U$2") (pin "17") (pinfunction "SUSPEND_17") (pintype "output"))
    )
    (net (code "72") (name "unconnected-(U$2-VPP-Pad16)") (class "Default")
      (node (ref "U$2") (pin "16") (pinfunction "VPP_16") (pintype "passive"))
    )
    (net (code "73") (name "unconnected-(U1-NC-Pad4)") (class "Default")
      (node (ref "U1") (pin "4") (pinfunction "NC_4") (pintype "bidirectional"))
    )
    (net (code "74") (name "unconnected-(U5-NC-Pad4)") (class "Default")
      (node (ref "U5") (pin "4") (pinfunction "NC_4") (pintype "bidirectional"))
    )
  )
)
